# ATtiny841_Basic5.net
KiCad netlist of a schematic drawn in EAGLE
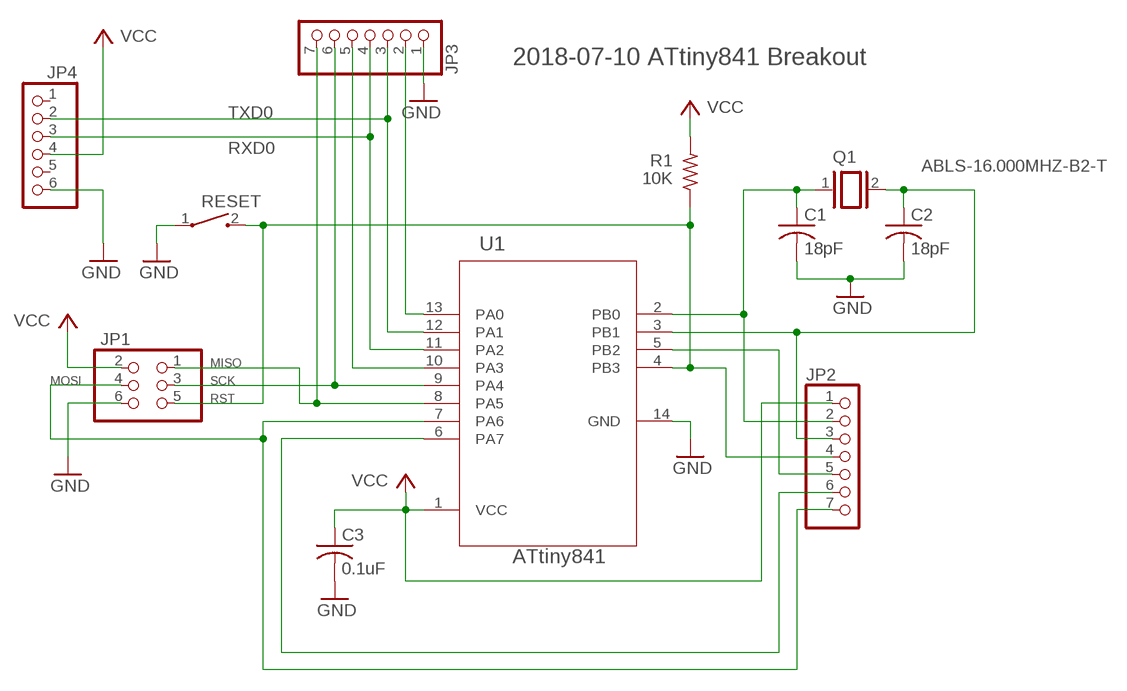
[diagram p0: schematic, sheet 1]

(export (version "E")
  (design (tool "Eeschema 10.0.6"))
  (components
    (comp (ref "C1")
      (value "18pF")
      (footprint "eagle-import:C0805")
      (libsource (lib "eagle-import") (part "C-USC0805"))
    )
    (comp (ref "C2")
      (value "18pF")
      (footprint "eagle-import:C0805")
      (libsource (lib "eagle-import") (part "C-USC0805"))
    )
    (comp (ref "C3")
      (value "0.1uF")
      (footprint "eagle-import:C0805")
      (libsource (lib "eagle-import") (part "C-USC0805"))
    )
    (comp (ref "JP1")
      (value "PINHD-2X3")
      (footprint "eagle-import:2X03")
      (libsource (lib "eagle-import") (part "PINHD-2X3"))
    )
    (comp (ref "JP2")
      (value "PINHD-1X7")
      (footprint "eagle-import:1X07")
      (libsource (lib "eagle-import") (part "PINHD-1X7"))
    )
    (comp (ref "JP3")
      (value "PINHD-1X7")
      (footprint "eagle-import:1X07")
      (libsource (lib "eagle-import") (part "PINHD-1X7"))
    )
    (comp (ref "JP4")
      (value "PINHD-1X6/90")
      (footprint "eagle-import:1X06_90")
      (libsource (lib "eagle-import") (part "PINHD-1X6/90"))
    )
    (comp (ref "Q1")
      (value "ABLS-16.000MHZ-B2-T")
      (footprint "eagle-import:XTAL1140X470X420")
      (libsource (lib "eagle-import") (part "XTAL/SXTAL-SMD"))
    )
    (comp (ref "R1")
      (value "10K")
      (footprint "eagle-import:R0805")
      (libsource (lib "eagle-import") (part "R-US_R0805"))
    )
    (comp (ref "RESET")
      (value "SPST-THROUGHHOLE")
      (footprint "eagle-import:SPST-THROUGHHOLE")
      (libsource (lib "eagle-import") (part "SPST-THROUGHHOLE"))
    )
    (comp (ref "U1")
      (value "ATtiny841")
      (footprint "eagle-import:SOIC127P599X175-14")
      (libsource (lib "eagle-import") (part "ATTINY841-SSUATTINY841-SO14"))
    )
  )
  (nets
    (net (code "1") (name "/MISO") (class "Default")
      (node (ref "JP1") (pin "1") (pinfunction "1_1") (pintype "passive"))
      (node (ref "JP3") (pin "7") (pinfunction "7_7") (pintype "passive"))
      (node (ref "U1") (pin "8") (pinfunction "PA5_8") (pintype "bidirectional"))
    )
    (net (code "2") (name "/MOSI") (class "Default")
      (node (ref "JP1") (pin "4") (pinfunction "4_4") (pintype "passive"))
      (node (ref "JP2") (pin "7") (pinfunction "7_7") (pintype "passive"))
      (node (ref "U1") (pin "7") (pinfunction "PA6_7") (pintype "bidirectional"))
    )
    (net (code "3") (name "/RST") (class "Default")
      (node (ref "JP1") (pin "5") (pinfunction "5_5") (pintype "passive"))
      (node (ref "JP2") (pin "4") (pinfunction "4_4") (pintype "passive"))
      (node (ref "R1") (pin "1") (pinfunction "1_1") (pintype "passive"))
      (node (ref "RESET") (pin "2") (pinfunction "2_2") (pintype "passive"))
      (node (ref "U1") (pin "4") (pinfunction "PB3_4") (pintype "bidirectional"))
    )
    (net (code "4") (name "/RXD0") (class "Default")
      (node (ref "JP3") (pin "4") (pinfunction "4_4") (pintype "passive"))
      (node (ref "JP4") (pin "3") (pinfunction "3_3") (pintype "passive"))
      (node (ref "U1") (pin "11") (pinfunction "PA2_11") (pintype "bidirectional"))
    )
    (net (code "5") (name "/SCK") (class "Default")
      (node (ref "JP1") (pin "3") (pinfunction "3_3") (pintype "passive"))
      (node (ref "JP3") (pin "6") (pinfunction "6_6") (pintype "passive"))
      (node (ref "U1") (pin "9") (pinfunction "PA4_9") (pintype "bidirectional"))
    )
    (net (code "6") (name "/TXD0") (class "Default")
      (node (ref "JP3") (pin "3") (pinfunction "3_3") (pintype "passive"))
      (node (ref "JP4") (pin "2") (pinfunction "2_2") (pintype "passive"))
      (node (ref "U1") (pin "12") (pinfunction "PA1_12") (pintype "bidirectional"))
    )
    (net (code "7") (name "GND") (class "Default")
      (node (ref "C1") (pin "2") (pinfunction "2_2") (pintype "passive"))
      (node (ref "C2") (pin "2") (pinfunction "2_2") (pintype "passive"))
      (node (ref "C3") (pin "2") (pinfunction "2_2") (pintype "passive"))
      (node (ref "JP1") (pin "6") (pinfunction "6_6") (pintype "passive"))
      (node (ref "JP3") (pin "1") (pinfunction "1_1") (pintype "passive"))
      (node (ref "JP4") (pin "6") (pinfunction "6_6") (pintype "passive"))
      (node (ref "RESET") (pin "1") (pinfunction "1_1") (pintype "passive"))
      (node (ref "U1") (pin "14") (pinfunction "GND_14") (pintype "power_in"))
    )
    (net (code "8") (name "Net-(U1-PA0)") (class "Default")
      (node (ref "JP3") (pin "2") (pinfunction "2_2") (pintype "passive"))
      (node (ref "U1") (pin "13") (pinfunction "PA0_13") (pintype "bidirectional"))
    )
    (net (code "9") (name "Net-(U1-PA3)") (class "Default")
      (node (ref "JP3") (pin "5") (pinfunction "5_5") (pintype "passive"))
      (node (ref "U1") (pin "10") (pinfunction "PA3_10") (pintype "bidirectional"))
    )
    (net (code "10") (name "Net-(U1-PA7)") (class "Default")
      (node (ref "JP2") (pin "6") (pinfunction "6_6") (pintype "passive"))
      (node (ref "U1") (pin "6") (pinfunction "PA7_6") (pintype "bidirectional"))
    )
    (net (code "11") (name "Net-(U1-PB0)") (class "Default")
      (node (ref "C1") (pin "1") (pinfunction "1_1") (pintype "passive"))
      (node (ref "JP2") (pin "2") (pinfunction "2_2") (pintype "passive"))
      (node (ref "Q1") (pin "1") (pinfunction "1_1") (pintype "passive"))
      (node (ref "U1") (pin "2") (pinfunction "PB0_2") (pintype "bidirectional"))
    )
    (net (code "12") (name "Net-(U1-PB1)") (class "Default")
      (node (ref "C2") (pin "1") (pinfunction "1_1") (pintype "passive"))
      (node (ref "JP2") (pin "3") (pinfunction "3_3") (pintype "passive"))
      (node (ref "Q1") (pin "2") (pinfunction "2_2") (pintype "passive"))
      (node (ref "U1") (pin "3") (pinfunction "PB1_3") (pintype "bidirectional"))
    )
    (net (code "13") (name "Net-(U1-PB2)") (class "Default")
      (node (ref "JP2") (pin "5") (pinfunction "5_5") (pintype "passive"))
      (node (ref "U1") (pin "5") (pinfunction "PB2_5") (pintype "bidirectional"))
    )
    (net (code "14") (name "VCC") (class "Default")
      (node (ref "C3") (pin "1") (pinfunction "1_1") (pintype "passive"))
      (node (ref "JP1") (pin "2") (pinfunction "2_2") (pintype "passive"))
      (node (ref "JP2") (pin "1") (pinfunction "1_1") (pintype "passive"))
      (node (ref "JP4") (pin "4") (pinfunction "4_4") (pintype "passive"))
      (node (ref "R1") (pin "2") (pinfunction "2_2") (pintype "passive"))
      (node (ref "U1") (pin "1") (pinfunction "VCC_1") (pintype "power_in"))
    )
    (net (code "15") (name "unconnected-(JP4-Pad1)") (class "Default")
      (node (ref "JP4") (pin "1") (pinfunction "1_1") (pintype "passive"))
    )
    (net (code "16") (name "unconnected-(JP4-Pad5)") (class "Default")
      (node (ref "JP4") (pin "5") (pinfunction "5_5") (pintype "passive"))
    )
  )
)
